# CSI_Camera_Bridge.net
KiCad netlist of a schematic drawn in Altium Designer
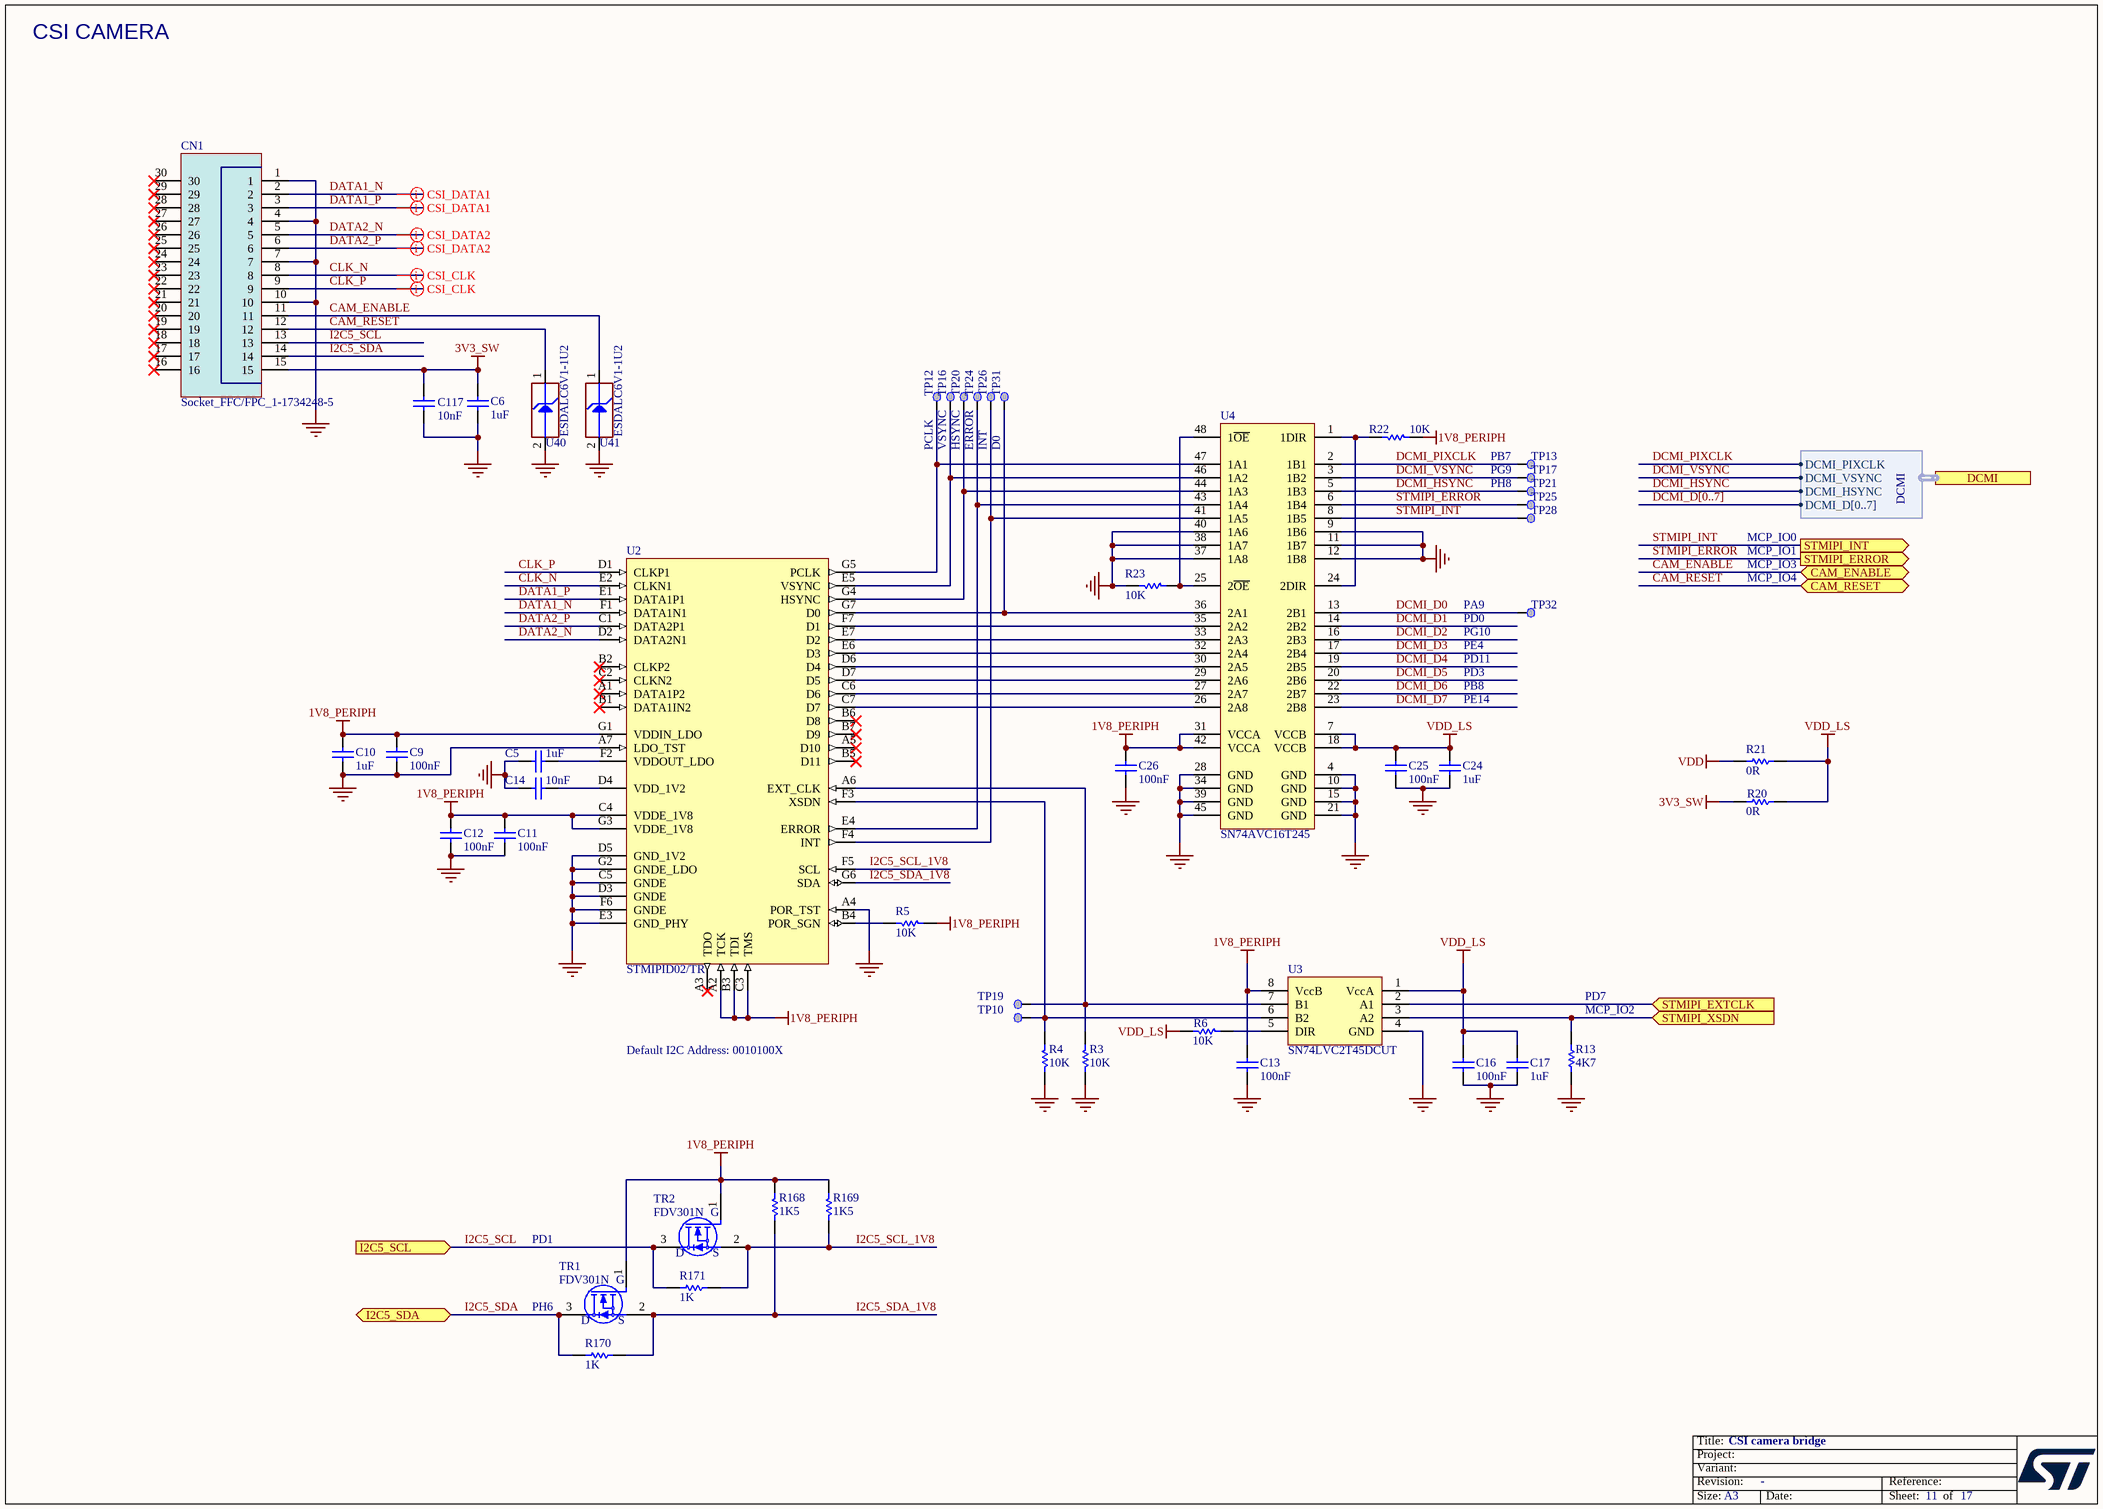
[diagram p0: CSI_Camera_Bridge.SchDoc]

(export (version "E")
  (design (tool "Eeschema 10.0.6"))
  (components
    (comp (ref "C5")
      (value "1uF")
      (footprint "C0201_MURATA_GRM033_H0P3")
      (description "Capacitor, MLCC, 1uF, 6.3V, X5R, +/-20%, 0201, T=0,3mm")
      (fields
        (field (name "INTERNAL_PART_NUMBER") "MCD-02377")
        (field (name "MANUFACTURER_PART_NUMBER") "GRM033R60J105MEA2")
      )
      (libsource (lib "MCD_PARTS_database") (part "Capacitor"))
    )
    (comp (ref "C6")
      (value "1uF")
      (footprint "C0402")
      (description "Capacitor, MLCC, 1uF, 25V, X5R, +/-10%, 0402, T=0.5mm")
      (fields
        (field (name "INTERNAL_PART_NUMBER") "MCD-00095")
        (field (name "MANUFACTURER_PART_NUMBER") "GRM155R61E105KA12")
      )
      (libsource (lib "MCD_PARTS_database") (part "Capacitor"))
    )
    (comp (ref "C9")
      (value "100nF")
      (footprint "C0402")
      (description "Capacitor, MLCC, 100nF, 16V, X7R, +/-10%, 0402, T=0.5mm")
      (fields
        (field (name "INTERNAL_PART_NUMBER") "MCD-00006")
        (field (name "MANUFACTURER_PART_NUMBER") "CC0402KRX7R7BB104")
      )
      (libsource (lib "MCD_PARTS_database") (part "Capacitor"))
    )
    (comp (ref "C10")
      (value "1uF")
      (footprint "C0201_MURATA_GRM033_H0P3")
      (description "Capacitor, MLCC, 1uF, 6.3V, X5R, +/-20%, 0201, T=0,3mm")
      (fields
        (field (name "INTERNAL_PART_NUMBER") "MCD-02377")
        (field (name "MANUFACTURER_PART_NUMBER") "GRM033R60J105MEA2")
      )
      (libsource (lib "MCD_PARTS_database") (part "Capacitor"))
    )
    (comp (ref "C11")
      (value "100nF")
      (footprint "C0402")
      (description "Capacitor, MLCC, 100nF, 16V, X7R, +/-10%, 0402, T=0.5mm")
      (fields
        (field (name "INTERNAL_PART_NUMBER") "MCD-00006")
        (field (name "MANUFACTURER_PART_NUMBER") "CC0402KRX7R7BB104")
      )
      (libsource (lib "MCD_PARTS_database") (part "Capacitor"))
    )
    (comp (ref "C12")
      (value "100nF")
      (footprint "C0402")
      (description "Capacitor, MLCC, 100nF, 16V, X7R, +/-10%, 0402, T=0.5mm")
      (fields
        (field (name "INTERNAL_PART_NUMBER") "MCD-00006")
        (field (name "MANUFACTURER_PART_NUMBER") "CC0402KRX7R7BB104")
      )
      (libsource (lib "MCD_PARTS_database") (part "Capacitor"))
    )
    (comp (ref "C13")
      (value "100nF")
      (footprint "C0402")
      (description "Capacitor, MLCC, 100nF, 16V, X7R, +/-10%, 0402, T=0.5mm")
      (fields
        (field (name "INTERNAL_PART_NUMBER") "MCD-00006")
        (field (name "MANUFACTURER_PART_NUMBER") "CC0402KRX7R7BB104")
      )
      (libsource (lib "MCD_PARTS_database") (part "Capacitor"))
    )
    (comp (ref "C14")
      (value "10nF")
      (footprint "C0402")
      (description "Capacitor, MLCC, 10nF, 50V, X7R, +/-10%, 0402, T=0.5mm")
      (fields
        (field (name "INTERNAL_PART_NUMBER") "MCD-02198")
        (field (name "MANUFACTURER_PART_NUMBER") "CC0402KRX7R9BB103")
      )
      (libsource (lib "MCD_PARTS_database") (part "Capacitor"))
    )
    (comp (ref "C16")
      (value "100nF")
      (footprint "C0402")
      (description "Capacitor, MLCC, 100nF, 16V, X7R, +/-10%, 0402, T=0.5mm")
      (fields
        (field (name "INTERNAL_PART_NUMBER") "MCD-00006")
        (field (name "MANUFACTURER_PART_NUMBER") "CC0402KRX7R7BB104")
      )
      (libsource (lib "MCD_PARTS_database") (part "Capacitor"))
    )
    (comp (ref "C17")
      (value "1uF")
      (footprint "C0201_MURATA_GRM033_H0P3")
      (description "Capacitor, MLCC, 1uF, 6.3V, X5R, +/-20%, 0201, T=0,3mm")
      (fields
        (field (name "INTERNAL_PART_NUMBER") "MCD-02377")
        (field (name "MANUFACTURER_PART_NUMBER") "GRM033R60J105MEA2")
      )
      (libsource (lib "MCD_PARTS_database") (part "Capacitor"))
    )
    (comp (ref "C24")
      (value "1uF")
      (footprint "C0201_MURATA_GRM033_H0P3")
      (description "Capacitor, MLCC, 1uF, 6.3V, X5R, +/-20%, 0201, T=0,3mm")
      (fields
        (field (name "INTERNAL_PART_NUMBER") "MCD-02377")
        (field (name "MANUFACTURER_PART_NUMBER") "GRM033R60J105MEA2")
      )
      (libsource (lib "MCD_PARTS_database") (part "Capacitor"))
    )
    (comp (ref "C25")
      (value "100nF")
      (footprint "C0402")
      (description "Capacitor, MLCC, 100nF, 16V, X7R, +/-10%, 0402, T=0.5mm")
      (fields
        (field (name "INTERNAL_PART_NUMBER") "MCD-00006")
        (field (name "MANUFACTURER_PART_NUMBER") "CC0402KRX7R7BB104")
      )
      (libsource (lib "MCD_PARTS_database") (part "Capacitor"))
    )
    (comp (ref "C26")
      (value "100nF")
      (footprint "C0402")
      (description "Capacitor, MLCC, 100nF, 16V, X7R, +/-10%, 0402, T=0.5mm")
      (fields
        (field (name "INTERNAL_PART_NUMBER") "MCD-00006")
        (field (name "MANUFACTURER_PART_NUMBER") "CC0402KRX7R7BB104")
      )
      (libsource (lib "MCD_PARTS_database") (part "Capacitor"))
    )
    (comp (ref "C117")
      (value "10nF")
      (footprint "C0402")
      (description "Capacitor, MLCC, 10nF, 50V, X7R, +/-10%, 0402, T=0.5mm")
      (fields (field (name "INTERNAL_PART_NUMBER") "MCD-02198") (field (name "MANUFACTURER") "YAGEO"))
      (libsource (lib "MCD_PARTS_database") (part "Capacitor"))
    )
    (comp (ref "CN1")
      (value "Socket_FFC/FPC_1-1734248-5")
      (footprint "CON_TE-CONNECTIVITY_1-1734248-5")
      (description "Socket_FFC/FPC, 15pins, 1mm ,VR, SMD, T=7.7mm")
      (fields
        (field (name "INTERNAL_PART_NUMBER") "MCD-02225")
        (field (name "MANUFACTURER") "TE CONNECTIVITY")
      )
      (libsource (lib "MCD_PARTS_database") (part "1-1734248-5"))
    )
    (comp (ref "R3")
      (value "10K")
      (footprint "R0402")
      (description "Resistor, 10K, 0402, +/-1%, 1/16W")
      (fields (field (name "INTERNAL_PART_NUMBER") "MCD-00053") (field (name "MANUFACTURER") "YAGEO"))
      (libsource (lib "MCD_PARTS_database") (part "Resistor"))
    )
    (comp (ref "R4")
      (value "10K")
      (footprint "R0402")
      (description "Resistor, 10K, 0402, +/-1%, 1/16W")
      (fields (field (name "INTERNAL_PART_NUMBER") "MCD-00053") (field (name "MANUFACTURER") "YAGEO"))
      (libsource (lib "MCD_PARTS_database") (part "Resistor"))
    )
    (comp (ref "R5")
      (value "10K")
      (footprint "R0402")
      (description "Resistor, 10K, 0402, +/-1%, 1/16W")
      (fields (field (name "INTERNAL_PART_NUMBER") "MCD-00053") (field (name "BMS_PART_NUMBER") "9131590"))
      (libsource (lib "MCD_PARTS_database") (part "Resistor"))
    )
    (comp (ref "R6")
      (value "10K")
      (footprint "R0402")
      (description "Resistor, 10K, 0402, +/-1%, 1/16W")
      (fields (field (name "INTERNAL_PART_NUMBER") "MCD-00053") (field (name "MANUFACTURER") "YAGEO"))
      (libsource (lib "MCD_PARTS_database") (part "Resistor"))
    )
    (comp (ref "R13")
      (value "4K7")
      (footprint "R0402")
      (description "Resistor, 4K7, 0402, +/-1%, 1/16W")
      (fields
        (field (name "INTERNAL_PART_NUMBER") "MCD-00065")
        (field (name "MANUFACTURER_PART_NUMBER") "RC0402FR-074K7L")
      )
      (libsource (lib "MCD_PARTS_database") (part "Resistor"))
    )
    (comp (ref "R20")
      (value "0R")
      (footprint "R0402")
      (description "Resistor, 0R, 0402, +/-5%, 1/16W")
      (fields (field (name "INTERNAL_PART_NUMBER") "MCD-00052") (field (name "MANUFACTURER") "YAGEO"))
      (libsource (lib "MCD_PARTS_database") (part "Resistor"))
    )
    (comp (ref "R21")
      (value "0R")
      (footprint "R0402")
      (description "Resistor, 0R, 0402, +/-5%, 1/16W")
      (fields (field (name "INTERNAL_PART_NUMBER") "MCD-00052") (field (name "MANUFACTURER") "YAGEO"))
      (libsource (lib "MCD_PARTS_database") (part "Resistor"))
    )
    (comp (ref "R22")
      (value "10K")
      (footprint "R0402")
      (description "Resistor, 10K, 0402, +/-1%, 1/16W")
      (fields (field (name "INTERNAL_PART_NUMBER") "MCD-00053") (field (name "MANUFACTURER") "YAGEO"))
      (libsource (lib "MCD_PARTS_database") (part "Resistor"))
    )
    (comp (ref "R23")
      (value "10K")
      (footprint "R0402")
      (description "Resistor, 10K, 0402, +/-1%, 1/16W")
      (fields (field (name "INTERNAL_PART_NUMBER") "MCD-00053") (field (name "MANUFACTURER") "YAGEO"))
      (libsource (lib "MCD_PARTS_database") (part "Resistor"))
    )
    (comp (ref "R168")
      (value "1K5")
      (footprint "R0402")
      (description "Resistor, 1K5, 0402, +/-1%, 1/16W")
      (fields (field (name "INTERNAL_PART_NUMBER") "MCD-00068") (field (name "MANUFACTURER") "YAGEO"))
      (libsource (lib "MCD_PARTS_database") (part "Resistor"))
    )
    (comp (ref "R169")
      (value "1K5")
      (footprint "R0402")
      (description "Resistor, 1K5, 0402, +/-1%, 1/16W")
      (fields (field (name "INTERNAL_PART_NUMBER") "MCD-00068") (field (name "MANUFACTURER") "YAGEO"))
      (libsource (lib "MCD_PARTS_database") (part "Resistor"))
    )
    (comp (ref "R170")
      (value "1K")
      (footprint "R0402")
      (description "Resistor, 1K, 0402, +/-1%,1/16W")
      (fields (field (name "INTERNAL_PART_NUMBER") "MCD-00061") (field (name "MANUFACTURER") "YAGEO"))
      (libsource (lib "MCD_PARTS_database") (part "Resistor"))
    )
    (comp (ref "R171")
      (value "1K")
      (footprint "R0402")
      (description "Resistor, 1K, 0402, +/-1%,1/16W")
      (fields (field (name "INTERNAL_PART_NUMBER") "MCD-00061") (field (name "MANUFACTURER") "YAGEO"))
      (libsource (lib "MCD_PARTS_database") (part "Resistor"))
    )
    (comp (ref "TP10")
      (value "Test Point")
      (footprint "TP_SMD_1MM")
      (description "Test Point 1mm")
      (fields (field (name "INTERNAL_PART_NUMBER") "MCD-00074"))
      (libsource (lib "") (part "Test Point_2"))
    )
    (comp (ref "TP12")
      (value "Test Point")
      (footprint "TP_SMD_1MM")
      (description "Test Point 1mm")
      (fields (field (name "INTERNAL_PART_NUMBER") "MCD-00074"))
      (libsource (lib "MCD_PARTS_database") (part "Test Point"))
    )
    (comp (ref "TP13")
      (value "Test Point")
      (footprint "TP_SMD_1MM")
      (description "Test Point 1mm")
      (fields (field (name "INTERNAL_PART_NUMBER") "MCD-00074"))
      (libsource (lib "") (part "Test Point_1"))
    )
    (comp (ref "TP16")
      (value "Test Point")
      (footprint "TP_SMD_1MM")
      (description "Test Point 1mm")
      (fields (field (name "INTERNAL_PART_NUMBER") "MCD-00074"))
      (libsource (lib "MCD_PARTS_database") (part "Test Point"))
    )
    (comp (ref "TP17")
      (value "Test Point")
      (footprint "TP_SMD_1MM")
      (description "Test Point 1mm")
      (fields (field (name "INTERNAL_PART_NUMBER") "MCD-00074"))
      (libsource (lib "") (part "Test Point_1"))
    )
    (comp (ref "TP19")
      (value "Test Point")
      (footprint "TP_SMD_1MM")
      (description "Test Point 1mm")
      (fields (field (name "INTERNAL_PART_NUMBER") "MCD-00074"))
      (libsource (lib "") (part "Test Point_2"))
    )
    (comp (ref "TP20")
      (value "Test Point")
      (footprint "TP_SMD_1MM")
      (description "Test Point 1mm")
      (fields (field (name "INTERNAL_PART_NUMBER") "MCD-00074"))
      (libsource (lib "MCD_PARTS_database") (part "Test Point"))
    )
    (comp (ref "TP21")
      (value "Test Point")
      (footprint "TP_SMD_1MM")
      (description "Test Point 1mm")
      (fields (field (name "INTERNAL_PART_NUMBER") "MCD-00074"))
      (libsource (lib "") (part "Test Point_1"))
    )
    (comp (ref "TP24")
      (value "Test Point")
      (footprint "TP_SMD_1MM")
      (description "Test Point 1mm")
      (fields (field (name "INTERNAL_PART_NUMBER") "MCD-00074"))
      (libsource (lib "MCD_PARTS_database") (part "Test Point"))
    )
    (comp (ref "TP25")
      (value "Test Point")
      (footprint "TP_SMD_1MM")
      (description "Test Point 1mm")
      (fields (field (name "INTERNAL_PART_NUMBER") "MCD-00074"))
      (libsource (lib "") (part "Test Point_1"))
    )
    (comp (ref "TP26")
      (value "Test Point")
      (footprint "TP_SMD_1MM")
      (description "Test Point 1mm")
      (fields (field (name "INTERNAL_PART_NUMBER") "MCD-00074"))
      (libsource (lib "MCD_PARTS_database") (part "Test Point"))
    )
    (comp (ref "TP28")
      (value "Test Point")
      (footprint "TP_SMD_1MM")
      (description "Test Point 1mm")
      (fields (field (name "INTERNAL_PART_NUMBER") "MCD-00074"))
      (libsource (lib "") (part "Test Point_1"))
    )
    (comp (ref "TP31")
      (value "Test Point")
      (footprint "TP_SMD_1MM")
      (description "Test Point 1mm")
      (fields (field (name "INTERNAL_PART_NUMBER") "MCD-00074"))
      (libsource (lib "MCD_PARTS_database") (part "Test Point"))
    )
    (comp (ref "TP32")
      (value "Test Point")
      (footprint "TP_SMD_1MM")
      (description "Test Point 1mm")
      (fields (field (name "INTERNAL_PART_NUMBER") "MCD-00074"))
      (libsource (lib "") (part "Test Point_1"))
    )
    (comp (ref "TR1")
      (value "FDV301N")
      (footprint "MOS_SOT23")
      (fields
        (field (name "INTERNAL_PART_NUMBER") "MCD-02156")
        (field (name "MANUFACTURER") "ON SEMICONDUCTOR")
        (field (name "Comment") "BSN20")
      )
      (libsource (lib "MCD_PARTS_database") (part "BSN20"))
    )
    (comp (ref "TR2")
      (value "FDV301N")
      (footprint "MOS_SOT23")
      (fields
        (field (name "INTERNAL_PART_NUMBER") "MCD-02156")
        (field (name "MANUFACTURER") "ON SEMICONDUCTOR")
        (field (name "Comment") "BSN20")
      )
      (libsource (lib "MCD_PARTS_database") (part "BSN20"))
    )
    (comp (ref "U2")
      (value "STMIPID02/TR")
      (footprint "ICC_VFBGA49_3X3_P040")
      (description "Dual mode MIPI CSI-2 / SMIA CCP2 de-serializer")
      (fields
        (field (name "INTERNAL_PART_NUMBER") "MCD-02213")
        (field (name "MANUFACTURER") "STMICROELECTRONICS")
      )
      (libsource (lib "MCD_PARTS_database") (part "STMIPID02"))
    )
    (comp (ref "U3")
      (value "SN74LVC2T45DCUT")
      (footprint "ICC_VSSOP8_DCU_R-PDSO-G8_2X2P30_P050")
      (description "Dual bit dual supply bus transceiver")
      (fields (field (name "INTERNAL_PART_NUMBER") "MCD-00264") (field (name "BMS_PART_NUMBER") "9169311"))
      (libsource (lib "MCD_PARTS_database") (part "SN74LVC2T45DCUT"))
    )
    (comp (ref "U4")
      (value "SN74AVC16T245")
      (footprint "ICC_TVSOP48_9P8X6P6_P040")
      (description "16-bit translating transceiver")
      (fields
        (field (name "INTERNAL_PART_NUMBER") "MCD-02226")
        (field (name "MANUFACTURER") "TEXAS INSTRUMENTS")
      )
      (libsource (lib "MCD_PARTS_database") (part "SN74AVC16T245DGG"))
    )
    (comp (ref "U40")
      (value "ESDALC6V1-1U2")
      (footprint "ESD_ST0201")
      (description "ESD protection 6V1")
      (fields (field (name "INTERNAL_PART_NUMBER") "MCD-00170") (field (name "BMS_PART_NUMBER") "9151132"))
      (libsource (lib "MCD_PARTS_database") (part "ESD-TRANSIL"))
    )
    (comp (ref "U41")
      (value "ESDALC6V1-1U2")
      (footprint "ESD_ST0201")
      (description "ESD protection 6V1")
      (fields (field (name "INTERNAL_PART_NUMBER") "MCD-00170") (field (name "BMS_PART_NUMBER") "9151132"))
      (libsource (lib "MCD_PARTS_database") (part "ESD-TRANSIL"))
    )
  )
  (nets
    (net (code "2") (name "/CAM_ENABLE") (class "Default")
      (node (ref "CN1") (pin "11") (pinfunction "11_11") (pintype "passive"))
      (node (ref "U41") (pin "1") (pinfunction "IO1_1") (pintype "passive"))
    )
    (net (code "3") (name "/CAM_RESET") (class "Default")
      (node (ref "CN1") (pin "12") (pinfunction "12_12") (pintype "passive"))
      (node (ref "U40") (pin "1") (pinfunction "IO1_1") (pintype "passive"))
    )
    (net (code "4") (name "/CLK_N") (class "Default")
      (node (ref "CN1") (pin "8") (pinfunction "8_8") (pintype "passive"))
      (node (ref "U2") (pin "E2") (pinfunction "CLKN1_E2") (pintype "input"))
    )
    (net (code "5") (name "/CLK_P") (class "Default")
      (node (ref "CN1") (pin "9") (pinfunction "9_9") (pintype "passive"))
      (node (ref "U2") (pin "D1") (pinfunction "CLKP1_D1") (pintype "input"))
    )
    (net (code "6") (name "/DATA1_N") (class "Default")
      (node (ref "CN1") (pin "2") (pinfunction "2_2") (pintype "passive"))
      (node (ref "U2") (pin "F1") (pinfunction "DATA1N1_F1") (pintype "input"))
    )
    (net (code "7") (name "/DATA1_P") (class "Default")
      (node (ref "CN1") (pin "3") (pinfunction "3_3") (pintype "passive"))
      (node (ref "U2") (pin "E1") (pinfunction "DATA1P1_E1") (pintype "input"))
    )
    (net (code "8") (name "/DATA2_N") (class "Default")
      (node (ref "CN1") (pin "5") (pinfunction "5_5") (pintype "passive"))
      (node (ref "U2") (pin "D2") (pinfunction "DATA2N1_D2") (pintype "input"))
    )
    (net (code "9") (name "/DATA2_P") (class "Default")
      (node (ref "CN1") (pin "6") (pinfunction "6_6") (pintype "passive"))
      (node (ref "U2") (pin "C1") (pinfunction "DATA2P1_C1") (pintype "input"))
    )
    (net (code "10") (name "/DCMI_D0") (class "Default")
      (node (ref "TP32") (pin "1") (pinfunction "1_1") (pintype "passive"))
      (node (ref "U4") (pin "13") (pinfunction "2B1_13") (pintype "passive"))
    )
    (net (code "11") (name "/DCMI_D1") (class "Default")
      (node (ref "U4") (pin "14") (pinfunction "2B2_14") (pintype "passive"))
    )
    (net (code "12") (name "/DCMI_D2") (class "Default")
      (node (ref "U4") (pin "16") (pinfunction "2B3_16") (pintype "passive"))
    )
    (net (code "13") (name "/DCMI_D3") (class "Default")
      (node (ref "U4") (pin "17") (pinfunction "2B4_17") (pintype "passive"))
    )
    (net (code "14") (name "/DCMI_D4") (class "Default")
      (node (ref "U4") (pin "19") (pinfunction "2B5_19") (pintype "passive"))
    )
    (net (code "15") (name "/DCMI_D5") (class "Default")
      (node (ref "U4") (pin "20") (pinfunction "2B6_20") (pintype "passive"))
    )
    (net (code "16") (name "/DCMI_D6") (class "Default")
      (node (ref "U4") (pin "22") (pinfunction "2B7_22") (pintype "passive"))
    )
    (net (code "17") (name "/DCMI_D7") (class "Default")
      (node (ref "U4") (pin "23") (pinfunction "2B8_23") (pintype "passive"))
    )
    (net (code "18") (name "/DCMI_HSYNC") (class "Default")
      (node (ref "TP21") (pin "1") (pinfunction "1_1") (pintype "passive"))
      (node (ref "U4") (pin "5") (pinfunction "1B3_5") (pintype "passive"))
    )
    (net (code "19") (name "/DCMI_PIXCLK") (class "Default")
      (node (ref "TP13") (pin "1") (pinfunction "1_1") (pintype "passive"))
      (node (ref "U4") (pin "2") (pinfunction "1B1_2") (pintype "passive"))
    )
    (net (code "20") (name "/DCMI_VSYNC") (class "Default")
      (node (ref "TP17") (pin "1") (pinfunction "1_1") (pintype "passive"))
      (node (ref "U4") (pin "3") (pinfunction "1B2_3") (pintype "passive"))
    )
    (net (code "22") (name "/I2C5_SCL") (class "Default")
      (node (ref "CN1") (pin "13") (pinfunction "13_13") (pintype "passive"))
      (node (ref "R171") (pin "2") (pinfunction "2_2") (pintype "passive"))
      (node (ref "TR2") (pin "3") (pinfunction "D_3") (pintype "passive"))
    )
    (net (code "23") (name "/I2C5_SCL_1V8") (class "Default")
      (node (ref "R169") (pin "1") (pinfunction "1_1") (pintype "passive"))
      (node (ref "R171") (pin "1") (pinfunction "1_1") (pintype "passive"))
      (node (ref "TR2") (pin "2") (pinfunction "S_2") (pintype "passive"))
      (node (ref "U2") (pin "F5") (pinfunction "SCL_F5") (pintype "input"))
    )
    (net (code "24") (name "/I2C5_SDA") (class "Default")
      (node (ref "CN1") (pin "14") (pinfunction "14_14") (pintype "passive"))
      (node (ref "R170") (pin "2") (pinfunction "2_2") (pintype "passive"))
      (node (ref "TR1") (pin "3") (pinfunction "D_3") (pintype "passive"))
    )
    (net (code "25") (name "/I2C5_SDA_1V8") (class "Default")
      (node (ref "R168") (pin "1") (pinfunction "1_1") (pintype "passive"))
      (node (ref "R170") (pin "1") (pinfunction "1_1") (pintype "passive"))
      (node (ref "TR1") (pin "2") (pinfunction "S_2") (pintype "passive"))
      (node (ref "U2") (pin "G6") (pinfunction "SDA_G6") (pintype "bidirectional"))
    )
    (net (code "26") (name "/STMIPI_ERROR") (class "Default")
      (node (ref "TP25") (pin "1") (pinfunction "1_1") (pintype "passive"))
      (node (ref "U4") (pin "6") (pinfunction "1B4_6") (pintype "passive"))
    )
    (net (code "27") (name "/STMIPI_EXTCLK") (class "Default")
      (node (ref "U3") (pin "2") (pinfunction "A1_2") (pintype "passive"))
    )
    (net (code "28") (name "/STMIPI_INT") (class "Default")
      (node (ref "TP28") (pin "1") (pinfunction "1_1") (pintype "passive"))
      (node (ref "U4") (pin "8") (pinfunction "1B5_8") (pintype "passive"))
    )
    (net (code "29") (name "/STMIPI_XSDN") (class "Default")
      (node (ref "R13") (pin "2") (pinfunction "2_2") (pintype "passive"))
      (node (ref "U3") (pin "3") (pinfunction "A2_3") (pintype "passive"))
    )
    (net (code "31") (name "1V8_PERIPH") (class "Default")
      (node (ref "C10") (pin "2") (pinfunction "2_2") (pintype "passive"))
      (node (ref "C11") (pin "2") (pinfunction "2_2") (pintype "passive"))
      (node (ref "C12") (pin "2") (pinfunction "2_2") (pintype "passive"))
      (node (ref "C13") (pin "2") (pinfunction "2_2") (pintype "passive"))
      (node (ref "C26") (pin "2") (pinfunction "2_2") (pintype "passive"))
      (node (ref "C9") (pin "2") (pinfunction "2_2") (pintype "passive"))
      (node (ref "R168") (pin "2") (pinfunction "2_2") (pintype "passive"))
      (node (ref "R169") (pin "2") (pinfunction "2_2") (pintype "passive"))
      (node (ref "R22") (pin "2") (pinfunction "2_2") (pintype "passive"))
      (node (ref "R5") (pin "1") (pinfunction "1_1") (pintype "passive"))
      (node (ref "TR1") (pin "1") (pinfunction "G_1") (pintype "passive"))
      (node (ref "TR2") (pin "1") (pinfunction "G_1") (pintype "passive"))
      (node (ref "U2") (pin "A2") (pinfunction "TCK_A2") (pintype "input"))
      (node (ref "U2") (pin "B3") (pinfunction "TDI_B3") (pintype "input"))
      (node (ref "U2") (pin "C3") (pinfunction "TMS_C3") (pintype "input"))
      (node (ref "U2") (pin "C4") (pinfunction "VDDE_1V8_C4") (pintype "power_in"))
      (node (ref "U2") (pin "G1") (pinfunction "VDDIN_LDO_G1") (pintype "power_in"))
      (node (ref "U2") (pin "G3") (pinfunction "VDDE_1V8_G3") (pintype "power_in"))
      (node (ref "U3") (pin "8") (pinfunction "VccB_8") (pintype "power_in"))
      (node (ref "U4") (pin "31") (pinfunction "VCCA_31") (pintype "passive"))
      (node (ref "U4") (pin "42") (pinfunction "VCCA_42") (pintype "passive"))
    )
    (net (code "32") (name "3V3_SW") (class "Default")
      (node (ref "C117") (pin "2") (pinfunction "2_2") (pintype "passive"))
      (node (ref "C6") (pin "2") (pinfunction "2_2") (pintype "passive"))
      (node (ref "CN1") (pin "15") (pinfunction "15_15") (pintype "passive"))
      (node (ref "R20") (pin "2") (pinfunction "2_2") (pintype "passive"))
    )
    (net (code "33") (name "GND") (class "Default")
      (node (ref "C10") (pin "1") (pinfunction "1_1") (pintype "passive"))
      (node (ref "C11") (pin "1") (pinfunction "1_1") (pintype "passive"))
      (node (ref "C117") (pin "1") (pinfunction "1_1") (pintype "passive"))
      (node (ref "C12") (pin "1") (pinfunction "1_1") (pintype "passive"))
      (node (ref "C13") (pin "1") (pinfunction "1_1") (pintype "passive"))
      (node (ref "C14") (pin "1") (pinfunction "1_1") (pintype "passive"))
      (node (ref "C16") (pin "1") (pinfunction "1_1") (pintype "passive"))
      (node (ref "C17") (pin "1") (pinfunction "1_1") (pintype "passive"))
      (node (ref "C24") (pin "1") (pinfunction "1_1") (pintype "passive"))
      (node (ref "C25") (pin "1") (pinfunction "1_1") (pintype "passive"))
      (node (ref "C26") (pin "1") (pinfunction "1_1") (pintype "passive"))
      (node (ref "C5") (pin "1") (pinfunction "1_1") (pintype "passive"))
      (node (ref "C6") (pin "1") (pinfunction "1_1") (pintype "passive"))
      (node (ref "C9") (pin "1") (pinfunction "1_1") (pintype "passive"))
      (node (ref "CN1") (pin "1") (pinfunction "1_1") (pintype "passive"))
      (node (ref "CN1") (pin "10") (pinfunction "10_10") (pintype "passive"))
      (node (ref "CN1") (pin "4") (pinfunction "4_4") (pintype "passive"))
      (node (ref "CN1") (pin "7") (pinfunction "7_7") (pintype "passive"))
      (node (ref "R13") (pin "1") (pinfunction "1_1") (pintype "passive"))
      (node (ref "R23") (pin "2") (pinfunction "2_2") (pintype "passive"))
      (node (ref "R3") (pin "2") (pinfunction "2_2") (pintype "passive"))
      (node (ref "R4") (pin "2") (pinfunction "2_2") (pintype "passive"))
      (node (ref "U2") (pin "A4") (pinfunction "POR_TST_A4") (pintype "input"))
      (node (ref "U2") (pin "A7") (pinfunction "LDO_TST_A7") (pintype "input"))
      (node (ref "U2") (pin "C5") (pinfunction "GNDE_C5") (pintype "power_in"))
      (node (ref "U2") (pin "D3") (pinfunction "GNDE_D3") (pintype "power_in"))
      (node (ref "U2") (pin "D5") (pinfunction "GND_1V2_D5") (pintype "power_in"))
      (node (ref "U2") (pin "E3") (pinfunction "GND_PHY_E3") (pintype "power_in"))
      (node (ref "U2") (pin "F6") (pinfunction "GNDE_F6") (pintype "power_in"))
      (node (ref "U2") (pin "G2") (pinfunction "GNDE_LDO_G2") (pintype "power_in"))
      (node (ref "U3") (pin "4") (pinfunction "GND_4") (pintype "power_in"))
      (node (ref "U4") (pin "10") (pinfunction "GND_10") (pintype "passive"))
      (node (ref "U4") (pin "11") (pinfunction "1B7_11") (pintype "passive"))
      (node (ref "U4") (pin "12") (pinfunction "1B8_12") (pintype "passive"))
      (node (ref "U4") (pin "15") (pinfunction "GND_15") (pintype "passive"))
      (node (ref "U4") (pin "21") (pinfunction "GND_21") (pintype "passive"))
      (node (ref "U4") (pin "28") (pinfunction "GND_28") (pintype "passive"))
      (node (ref "U4") (pin "34") (pinfunction "GND_34") (pintype "passive"))
      (node (ref "U4") (pin "37") (pinfunction "1A8_37") (pintype "passive"))
      (node (ref "U4") (pin "38") (pinfunction "1A7_38") (pintype "passive"))
      (node (ref "U4") (pin "39") (pinfunction "GND_39") (pintype "passive"))
      (node (ref "U4") (pin "4") (pinfunction "GND_4") (pintype "passive"))
      (node (ref "U4") (pin "40") (pinfunction "1A6_40") (pintype "passive"))
      (node (ref "U4") (pin "45") (pinfunction "GND_45") (pintype "passive"))
      (node (ref "U4") (pin "9") (pinfunction "1B6_9") (pintype "passive"))
      (node (ref "U40") (pin "2") (pinfunction "GND_2") (pintype "passive"))
      (node (ref "U41") (pin "2") (pinfunction "GND_2") (pintype "passive"))
    )
    (net (code "34") (name "Net-(U2-D0)") (class "Default")
      (node (ref "TP31") (pin "1") (pinfunction "1_1") (pintype "passive"))
      (node (ref "U2") (pin "G7") (pinfunction "D0_G7") (pintype "output"))
      (node (ref "U4") (pin "36") (pinfunction "2A1_36") (pintype "passive"))
    )
    (net (code "35") (name "Net-(U2-D1)") (class "Default")
      (node (ref "U2") (pin "F7") (pinfunction "D1_F7") (pintype "output"))
      (node (ref "U4") (pin "35") (pinfunction "2A2_35") (pintype "passive"))
    )
    (net (code "36") (name "Net-(U2-D2)") (class "Default")
      (node (ref "U2") (pin "E7") (pinfunction "D2_E7") (pintype "output"))
      (node (ref "U4") (pin "33") (pinfunction "2A3_33") (pintype "passive"))
    )
    (net (code "37") (name "Net-(U2-D3)") (class "Default")
      (node (ref "U2") (pin "E6") (pinfunction "D3_E6") (pintype "output"))
      (node (ref "U4") (pin "32") (pinfunction "2A4_32") (pintype "passive"))
    )
    (net (code "38") (name "Net-(U2-D4)") (class "Default")
      (node (ref "U2") (pin "D6") (pinfunction "D4_D6") (pintype "output"))
      (node (ref "U4") (pin "30") (pinfunction "2A5_30") (pintype "passive"))
    )
    (net (code "39") (name "Net-(U2-D5)") (class "Default")
      (node (ref "U2") (pin "D7") (pinfunction "D5_D7") (pintype "output"))
      (node (ref "U4") (pin "29") (pinfunction "2A6_29") (pintype "passive"))
    )
    (net (code "40") (name "Net-(U2-D6)") (class "Default")
      (node (ref "U2") (pin "C6") (pinfunction "D6_C6") (pintype "output"))
      (node (ref "U4") (pin "27") (pinfunction "2A7_27") (pintype "passive"))
    )
    (net (code "41") (name "Net-(U2-D7)") (class "Default")
      (node (ref "U2") (pin "C7") (pinfunction "D7_C7") (pintype "output"))
      (node (ref "U4") (pin "26") (pinfunction "2A8_26") (pintype "passive"))
    )
    (net (code "42") (name "Net-(U2-ERROR)") (class "Default")
      (node (ref "TP24") (pin "1") (pinfunction "1_1") (pintype "passive"))
      (node (ref "U2") (pin "E4") (pinfunction "ERROR_E4") (pintype "output"))
      (node (ref "U4") (pin "43") (pinfunction "1A4_43") (pintype "passive"))
    )
    (net (code "43") (name "Net-(U2-EXT_CLK)") (class "Default")
      (node (ref "R3") (pin "1") (pinfunction "1_1") (pintype "passive"))
      (node (ref "TP19") (pin "1") (pinfunction "1_1") (pintype "passive"))
      (node (ref "U2") (pin "A6") (pinfunction "EXT_CLK_A6") (pintype "input"))
      (node (ref "U3") (pin "7") (pinfunction "B1_7") (pintype "passive"))
    )
    (net (code "44") (name "Net-(U2-HSYNC)") (class "Default")
      (node (ref "TP20") (pin "1") (pinfunction "1_1") (pintype "passive"))
      (node (ref "U2") (pin "G4") (pinfunction "HSYNC_G4") (pintype "output"))
      (node (ref "U4") (pin "44") (pinfunction "1A3_44") (pintype "passive"))
    )
    (net (code "45") (name "Net-(U2-INT)") (class "Default")
      (node (ref "TP26") (pin "1") (pinfunction "1_1") (pintype "passive"))
      (node (ref "U2") (pin "F4") (pinfunction "INT_F4") (pintype "output"))
      (node (ref "U4") (pin "41") (pinfunction "1A5_41") (pintype "passive"))
    )
    (net (code "46") (name "Net-(U2-PCLK)") (class "Default")
      (node (ref "TP12") (pin "1") (pinfunction "1_1") (pintype "passive"))
      (node (ref "U2") (pin "G5") (pinfunction "PCLK_G5") (pintype "output"))
      (node (ref "U4") (pin "47") (pinfunction "1A1_47") (pintype "passive"))
    )
    (net (code "47") (name "Net-(U2-POR_SGN)") (class "Default")
      (node (ref "R5") (pin "2") (pinfunction "2_2") (pintype "passive"))
      (node (ref "U2") (pin "B4") (pinfunction "POR_SGN_B4") (pintype "bidirectional"))
    )
    (net (code "48") (name "Net-(U2-VDDOUT_LDO)") (class "Default")
      (node (ref "C5") (pin "2") (pinfunction "2_2") (pintype "passive"))
      (node (ref "U2") (pin "F2") (pinfunction "VDDOUT_LDO_F2") (pintype "power_in"))
    )
    (net (code "49") (name "Net-(U2-VDD_1V2)") (class "Default")
      (node (ref "C14") (pin "2") (pinfunction "2_2") (pintype "passive"))
      (node (ref "U2") (pin "D4") (pinfunction "VDD_1V2_D4") (pintype "power_in"))
    )
    (net (code "50") (name "Net-(U2-VSYNC)") (class "Default")
      (node (ref "TP16") (pin "1") (pinfunction "1_1") (pintype "passive"))
      (node (ref "U2") (pin "E5") (pinfunction "VSYNC_E5") (pintype "output"))
      (node (ref "U4") (pin "46") (pinfunction "1A2_46") (pintype "passive"))
    )
    (net (code "51") (name "Net-(U2-XSDN)") (class "Default")
      (node (ref "R4") (pin "1") (pinfunction "1_1") (pintype "passive"))
      (node (ref "TP10") (pin "1") (pinfunction "1_1") (pintype "passive"))
      (node (ref "U2") (pin "F3") (pinfunction "XSDN_F3") (pintype "input"))
      (node (ref "U3") (pin "6") (pinfunction "B2_6") (pintype "passive"))
    )
    (net (code "52") (name "Net-(U3-DIR)") (class "Default")
      (node (ref "R6") (pin "1") (pinfunction "1_1") (pintype "passive"))
      (node (ref "U3") (pin "5") (pinfunction "DIR_5") (pintype "passive"))
    )
    (net (code "53") (name "Net-(U4-1DIR)") (class "Default")
      (node (ref "R22") (pin "1") (pinfunction "1_1") (pintype "passive"))
      (node (ref "U4") (pin "1") (pinfunction "1DIR_1") (pintype "passive"))
      (node (ref "U4") (pin "24") (pinfunction "2DIR_24") (pintype "passive"))
    )
    (net (code "54") (name "Net-(U4-1~{OE})") (class "Default")
      (node (ref "R23") (pin "1") (pinfunction "1_1") (pintype "passive"))
      (node (ref "U4") (pin "25") (pinfunction "2~{OE}_25") (pintype "passive"))
      (node (ref "U4") (pin "48") (pinfunction "1~{OE}_48") (pintype "passive"))
    )
    (net (code "55") (name "VDD") (class "Default")
      (node (ref "R21") (pin "2") (pinfunction "2_2") (pintype "passive"))
    )
    (net (code "56") (name "VDD_LS") (class "Default")
      (node (ref "C16") (pin "2") (pinfunction "2_2") (pintype "passive"))
      (node (ref "C17") (pin "2") (pinfunction "2_2") (pintype "passive"))
      (node (ref "C24") (pin "2") (pinfunction "2_2") (pintype "passive"))
      (node (ref "C25") (pin "2") (pinfunction "2_2") (pintype "passive"))
      (node (ref "R20") (pin "1") (pinfunction "1_1") (pintype "passive"))
      (node (ref "R21") (pin "1") (pinfunction "1_1") (pintype "passive"))
      (node (ref "R6") (pin "2") (pinfunction "2_2") (pintype "passive"))
      (node (ref "U3") (pin "1") (pinfunction "VccA_1") (pintype "power_in"))
      (node (ref "U4") (pin "18") (pinfunction "VCCB_18") (pintype "passive"))
      (node (ref "U4") (pin "7") (pinfunction "VCCB_7") (pintype "passive"))
    )
    (net (code "57") (name "unconnected-(CN1-Pad16)") (class "Default")
      (node (ref "CN1") (pin "16") (pinfunction "16_16") (pintype "passive+no_connect"))
    )
    (net (code "58") (name "unconnected-(CN1-Pad17)") (class "Default")
      (node (ref "CN1") (pin "17") (pinfunction "17_17") (pintype "passive+no_connect"))
    )
    (net (code "59") (name "unconnected-(CN1-Pad18)") (class "Default")
      (node (ref "CN1") (pin "18") (pinfunction "18_18") (pintype "passive+no_connect"))
    )
    (net (code "60") (name "unconnected-(CN1-Pad19)") (class "Default")
      (node (ref "CN1") (pin "19") (pinfunction "19_19") (pintype "passive+no_connect"))
    )
    (net (code "61") (name "unconnected-(CN1-Pad20)") (class "Default")
      (node (ref "CN1") (pin "20") (pinfunction "20_20") (pintype "passive+no_connect"))
    )
    (net (code "62") (name "unconnected-(CN1-Pad21)") (class "Default")
      (node (ref "CN1") (pin "21") (pinfunction "21_21") (pintype "passive+no_connect"))
    )
    (net (code "63") (name "unconnected-(CN1-Pad22)") (class "Default")
      (node (ref "CN1") (pin "22") (pinfunction "22_22") (pintype "passive+no_connect"))
    )
    (net (code "64") (name "unconnected-(CN1-Pad23)") (class "Default")
      (node (ref "CN1") (pin "23") (pinfunction "23_23") (pintype "passive+no_connect"))
    )
    (net (code "65") (name "unconnected-(CN1-Pad24)") (class "Default")
      (node (ref "CN1") (pin "24") (pinfunction "24_24") (pintype "passive+no_connect"))
    )
    (net (code "66") (name "unconnected-(CN1-Pad25)") (class "Default")
      (node (ref "CN1") (pin "25") (pinfunction "25_25") (pintype "passive+no_connect"))
    )
    (net (code "67") (name "unconnected-(CN1-Pad26)") (class "Default")
      (node (ref "CN1") (pin "26") (pinfunction "26_26") (pintype "passive+no_connect"))
    )
    (net (code "68") (name "unconnected-(CN1-Pad27)") (class "Default")
      (node (ref "CN1") (pin "27") (pinfunction "27_27") (pintype "passive+no_connect"))
    )
    (net (code "69") (name "unconnected-(CN1-Pad28)") (class "Default")
      (node (ref "CN1") (pin "28") (pinfunction "28_28") (pintype "passive+no_connect"))
    )
    (net (code "70") (name "unconnected-(CN1-Pad29)") (class "Default")
      (node (ref "CN1") (pin "29") (pinfunction "29_29") (pintype "passive+no_connect"))
    )
    (net (code "71") (name "unconnected-(CN1-Pad30)") (class "Default")
      (node (ref "CN1") (pin "30") (pinfunction "30_30") (pintype "passive+no_connect"))
    )
    (net (code "72") (name "unconnected-(U2-CLKN2-PadC2)") (class "Default")
      (node (ref "U2") (pin "C2") (pinfunction "CLKN2_C2") (pintype "input+no_connect"))
    )
    (net (code "73") (name "unconnected-(U2-CLKP2-PadB2)") (class "Default")
      (node (ref "U2") (pin "B2") (pinfunction "CLKP2_B2") (pintype "input+no_connect"))
    )
    (net (code "74") (name "unconnected-(U2-D8-PadB6)") (class "Default")
      (node (ref "U2") (pin "B6") (pinfunction "D8_B6") (pintype "output+no_connect"))
    )
    (net (code "75") (name "unconnected-(U2-D9-PadB7)") (class "Default")
      (node (ref "U2") (pin "B7") (pinfunction "D9_B7") (pintype "output+no_connect"))
    )
    (net (code "76") (name "unconnected-(U2-D10-PadA5)") (class "Default")
      (node (ref "U2") (pin "A5") (pinfunction "D10_A5") (pintype "output+no_connect"))
    )
    (net (code "77") (name "unconnected-(U2-D11-PadB5)") (class "Default")
      (node (ref "U2") (pin "B5") (pinfunction "D11_B5") (pintype "output+no_connect"))
    )
    (net (code "78") (name "unconnected-(U2-DATA1IN2-PadB1)") (class "Default")
      (node (ref "U2") (pin "B1") (pinfunction "DATA1IN2_B1") (pintype "input+no_connect"))
    )
    (net (code "79") (name "unconnected-(U2-DATA1P2-PadA1)") (class "Default")
      (node (ref "U2") (pin "A1") (pinfunction "DATA1P2_A1") (pintype "input+no_connect"))
    )
    (net (code "80") (name "unconnected-(U2-TDO-PadA3)") (class "Default")
      (node (ref "U2") (pin "A3") (pinfunction "TDO_A3") (pintype "output+no_connect"))
    )
  )
)
